# Second_vehicle.net
KiCad netlist of a schematic drawn in EasyEDA
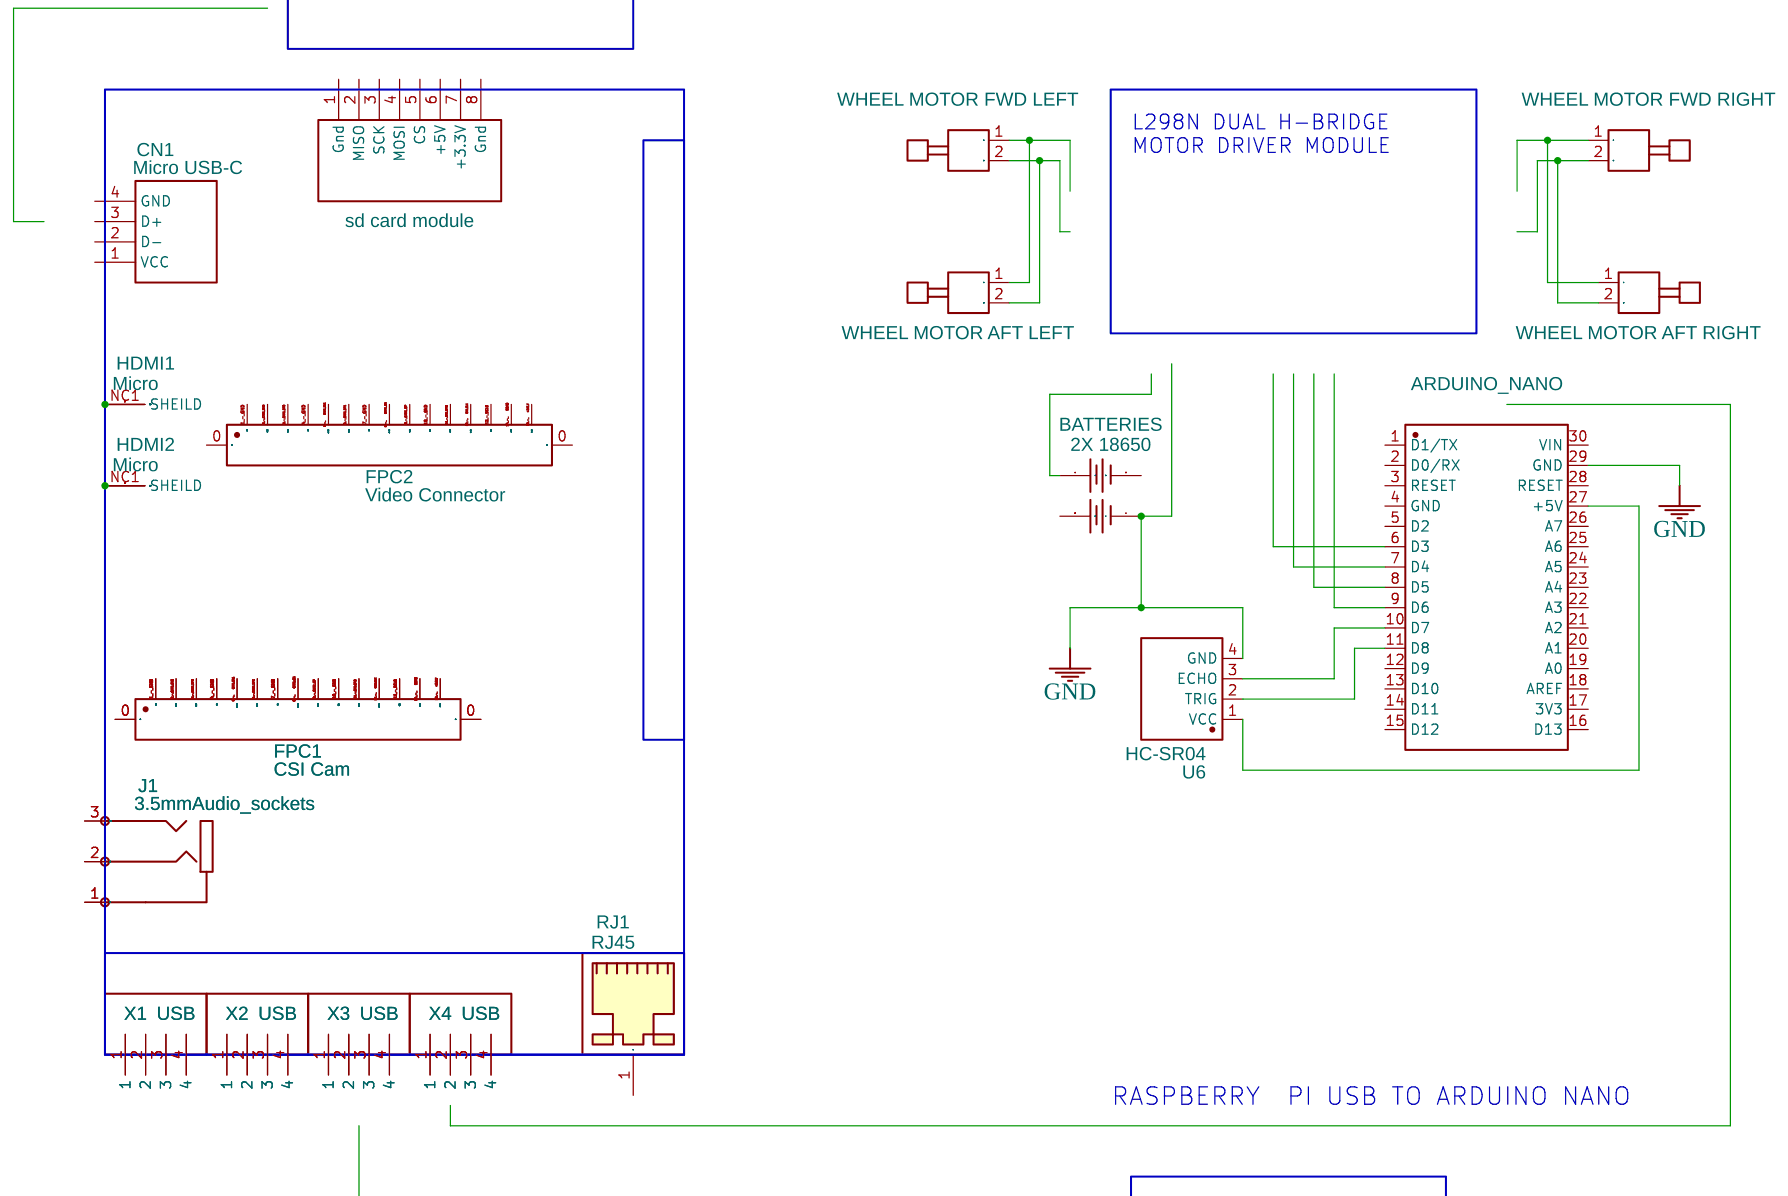
[diagram p0: schematic sheet]

(export (version "E")
  (design (tool "Eeschema 10.0.6"))
  (components
    (comp (ref "BATTERIES")
      (value "2X 18650")
      (fields
        (field (name "Manufacturer Part") "BH-18650-A1BJ034")
        (field (name "Manufacturer") "MYOUNG(美阳)")
      )
      (libsource (lib "") (part "BH-18650-A1BJ034"))
    )
    (comp (ref "CN1")
      (value "Micro USB-C")
      (fields (field (name "Manufacturer Part") "USB-CONN-AF-LCP") (field (name "Manufacturer") "ValuePro"))
      (libsource (lib "") (part "Unknown_90_-1680"))
    )
    (comp (ref "FPC1")
      (value "CSI Cam")
      (fields (field (name "Manufacturer Part") "F1003WR-S-15PNLNG1GB0R") (field (name "Manufacturer") "HR"))
      (libsource (lib "") (part "Unknown_150_-1435"))
    )
    (comp (ref "FPC2")
      (value "Video Connector")
      (fields (field (name "Manufacturer Part") "F1003WR-S-15PNLNG1GB0R") (field (name "Manufacturer") "HR"))
      (libsource (lib "") (part "Unknown_195_-1570"))
    )
    (comp (ref "HDMI1")
      (value "Micro")
      (fields (field (name "Manufacturer Part") "?"))
      (libsource (lib "") (part "Unknown_75_-1590"))
    )
    (comp (ref "HDMI2")
      (value "Micro")
      (fields (field (name "Manufacturer Part") "?"))
      (libsource (lib "") (part "Unknown_75_-1550"))
    )
    (comp (ref "J1")
      (value "3.5mmAudio_sockets")
      (fields
        (field (name "Manufacturer Part") "3.5mmAudio sockets PJ325")
        (field (name "Manufacturer") "BOOMELE")
      )
      (libsource (lib "") (part "Unknown_55_-1365"))
    )
    (comp (ref "RJ1")
      (value "RJ45")
      (fields (field (name "Manufacturer Part") "?"))
      (libsource (lib "") (part "Unknown_325_-1280"))
    )
    (comp (ref "U1") (value "ARDUINO_NANO") (libsource (lib "") (part "ARDUINO_NANO")))
    (comp (ref "U2")
      (value "WHEEL MOTOR FWD LEFT")
      (fields (field (name "Manufacturer Part") "LCM04084521-B1") (field (name "Manufacturer") "LEADER(立得)"))
      (libsource (lib "") (part "LCM04084521-B1_1"))
    )
    (comp (ref "U3")
      (value "WHEEL MOTOR FWD RIGHT")
      (fields (field (name "Manufacturer Part") "LCM04084521-B1") (field (name "Manufacturer") "LEADER(立得)"))
      (libsource (lib "") (part "LCM04084521-B1"))
    )
    (comp (ref "U4")
      (value "WHEEL MOTOR AFT LEFT")
      (fields (field (name "Manufacturer Part") "LCM04084521-B1") (field (name "Manufacturer") "LEADER(立得)"))
      (libsource (lib "") (part "LCM04084521-B1_1"))
    )
    (comp (ref "U5")
      (value "WHEEL MOTOR AFT RIGHT")
      (fields (field (name "Manufacturer Part") "LCM04084521-B1") (field (name "Manufacturer") "LEADER(立得)"))
      (libsource (lib "") (part "LCM04084521-B1"))
    )
    (comp (ref "U6")
      (value "HC-SR04")
      (fields (field (name "Manufacturer") "Universal Microelectronics"))
      (libsource (lib "") (part "HC-SR04"))
    )
    (comp (ref "U7") (value "sd card module") (libsource (lib "") (part "Unknown_205_-1735")))
    (comp (ref "X1")
      (value "USB")
      (fields (field (name "Manufacturer Part") "?"))
      (libsource (lib "") (part "Unknown_80_-1275"))
    )
    (comp (ref "X2")
      (value "USB")
      (fields (field (name "Manufacturer Part") "?"))
      (libsource (lib "") (part "Unknown_130_-1275"))
    )
    (comp (ref "X3")
      (value "USB")
      (fields (field (name "Manufacturer Part") "?"))
      (libsource (lib "") (part "Unknown_180_-1275"))
    )
    (comp (ref "X4")
      (value "USB")
      (fields (field (name "Manufacturer Part") "?"))
      (libsource (lib "") (part "Unknown_230_-1275"))
    )
  )
  (nets
    (net (code "1") (name "GND") (class "Default")
      (node (ref "BATTERIES") (pin "4") (pinfunction "4_4") (pintype "input"))
      (node (ref "U1") (pin "29") (pinfunction "GND_29") (pintype "unspecified"))
      (node (ref "U6") (pin "4") (pinfunction "GND_4") (pintype "unspecified"))
    )
    (net (code "2") (name "Net-(HDMI1-SHEILD-PadNC1)") (class "Default")
      (node (ref "HDMI1") (pin "NC1") (pinfunction "SHEILD_NC1") (pintype "bidirectional"))
      (node (ref "HDMI1") (pin "NC2") (pinfunction "SHEILD_NC2") (pintype "bidirectional"))
      (node (ref "HDMI1") (pin "NC3") (pinfunction "SHEILD_NC3") (pintype "bidirectional"))
      (node (ref "HDMI1") (pin "NC4") (pinfunction "SHEILD_NC4") (pintype "bidirectional"))
    )
    (net (code "3") (name "Net-(HDMI2-SHEILD-PadNC1)") (class "Default")
      (node (ref "HDMI2") (pin "NC1") (pinfunction "SHEILD_NC1") (pintype "bidirectional"))
      (node (ref "HDMI2") (pin "NC2") (pinfunction "SHEILD_NC2") (pintype "bidirectional"))
      (node (ref "HDMI2") (pin "NC3") (pinfunction "SHEILD_NC3") (pintype "bidirectional"))
      (node (ref "HDMI2") (pin "NC4") (pinfunction "SHEILD_NC4") (pintype "bidirectional"))
    )
    (net (code "4") (name "Net-(U1-+5V)") (class "Default")
      (node (ref "U1") (pin "27") (pinfunction "+5V_27") (pintype "unspecified"))
      (node (ref "U6") (pin "1") (pinfunction "VCC_1") (pintype "unspecified"))
    )
    (net (code "5") (name "Net-(U1-D7)") (class "Default")
      (node (ref "U1") (pin "10") (pinfunction "D7_10") (pintype "unspecified"))
      (node (ref "U6") (pin "3") (pinfunction "ECHO_3") (pintype "unspecified"))
    )
    (net (code "6") (name "Net-(U1-D8)") (class "Default")
      (node (ref "U1") (pin "11") (pinfunction "D8_11") (pintype "unspecified"))
      (node (ref "U6") (pin "2") (pinfunction "TRIG_2") (pintype "unspecified"))
    )
    (net (code "7") (name "Net-(U2-Pad1)") (class "Default")
      (node (ref "U2") (pin "1") (pinfunction "1_1") (pintype "unspecified"))
      (node (ref "U4") (pin "1") (pinfunction "1_1") (pintype "unspecified"))
    )
    (net (code "8") (name "Net-(U2-Pad2)") (class "Default")
      (node (ref "U2") (pin "2") (pinfunction "2_2") (pintype "unspecified"))
      (node (ref "U4") (pin "2") (pinfunction "2_2") (pintype "unspecified"))
    )
    (net (code "9") (name "Net-(U3-Pad1)") (class "Default")
      (node (ref "U3") (pin "1") (pinfunction "1_1") (pintype "unspecified"))
      (node (ref "U5") (pin "1") (pinfunction "1_1") (pintype "unspecified"))
    )
    (net (code "10") (name "Net-(U3-Pad2)") (class "Default")
      (node (ref "U3") (pin "2") (pinfunction "2_2") (pintype "unspecified"))
      (node (ref "U5") (pin "2") (pinfunction "2_2") (pintype "unspecified"))
    )
    (net (code "11") (name "unconnected-(BATTERIES-Pad1)") (class "Default")
      (node (ref "BATTERIES") (pin "1") (pinfunction "1_1") (pintype "input"))
    )
    (net (code "12") (name "unconnected-(BATTERIES-Pad2)") (class "Default")
      (node (ref "BATTERIES") (pin "2") (pinfunction "2_2") (pintype "input"))
    )
    (net (code "13") (name "unconnected-(BATTERIES-Pad3)") (class "Default")
      (node (ref "BATTERIES") (pin "3") (pinfunction "3_3") (pintype "input"))
    )
    (net (code "14") (name "unconnected-(CN1-D+-Pad3)") (class "Default")
      (node (ref "CN1") (pin "3") (pinfunction "D+_3") (pintype "input"))
    )
    (net (code "15") (name "unconnected-(CN1-D--Pad2)") (class "Default")
      (node (ref "CN1") (pin "2") (pinfunction "D-_2") (pintype "input"))
    )
    (net (code "16") (name "unconnected-(CN1-GND-Pad4)") (class "Default")
      (node (ref "CN1") (pin "4") (pinfunction "GND_4") (pintype "input"))
    )
    (net (code "17") (name "unconnected-(CN1-VCC-Pad1)") (class "Default")
      (node (ref "CN1") (pin "1") (pinfunction "VCC_1") (pintype "input"))
    )
    (net (code "18") (name "unconnected-(FPC1-Pad0)") (class "Default")
      (node (ref "FPC1") (pin "0") (pinfunction "0_0") (pintype "unspecified"))
    )
    (net (code "19") (name "unconnected-(FPC1-Pad0)_1") (class "Default")
      (node (ref "FPC1") (pin "0") (pinfunction "0_0") (pintype "unspecified"))
    )
    (net (code "20") (name "unconnected-(FPC1-Pad1_-_GND)") (class "Default")
      (node (ref "FPC1") (pin "1_-_GND") (pinfunction "1_-_GND_1_-_GND") (pintype "unspecified"))
    )
    (net (code "21") (name "unconnected-(FPC1-Pad2_-_CAM1_DN0)") (class "Default")
      (node (ref "FPC1") (pin "2_-_CAM1_DN0") (pinfunction "2_-_CAM1_DN0_2_-_CAM1_DN0") (pintype "unspecified"))
    )
    (net (code "22") (name "unconnected-(FPC1-Pad3_-_CAM1_DP0)") (class "Default")
      (node (ref "FPC1") (pin "3_-_CAM1_DP0") (pinfunction "3_-_CAM1_DP0_3_-_CAM1_DP0") (pintype "unspecified"))
    )
    (net (code "23") (name "unconnected-(FPC1-Pad4_-_GND)") (class "Default")
      (node (ref "FPC1") (pin "4_-_GND") (pinfunction "4_-_GND_4_-_GND") (pintype "unspecified"))
    )
    (net (code "24") (name "unconnected-(FPC1-Pad5_-_	CAM1_DN1)") (class "Default")
      (node (ref "FPC1") (pin "5_-_	CAM1_DN1") (pinfunction "5_-_	CAM1_DN1_5_-_	CAM1_DN1") (pintype "unspecified"))
    )
    (net (code "25") (name "unconnected-(FPC1-Pad6_-_CAM1_DP1)") (class "Default")
      (node (ref "FPC1") (pin "6_-_CAM1_DP1") (pinfunction "6_-_CAM1_DP1_6_-_CAM1_DP1") (pintype "unspecified"))
    )
    (net (code "26") (name "unconnected-(FPC1-Pad7_-_GND)") (class "Default")
      (node (ref "FPC1") (pin "7_-_GND") (pinfunction "7_-_GND_7_-_GND") (pintype "unspecified"))
    )
    (net (code "27") (name "unconnected-(FPC1-Pad8_-_	CAM1_CN)") (class "Default")
      (node (ref "FPC1") (pin "8_-_	CAM1_CN") (pinfunction "8_-_	CAM1_CN_8_-_	CAM1_CN") (pintype "unspecified"))
    )
    (net (code "28") (name "unconnected-(FPC1-Pad9_-_CAM1_CP)") (class "Default")
      (node (ref "FPC1") (pin "9_-_CAM1_CP") (pinfunction "9_-_CAM1_CP_9_-_CAM1_CP") (pintype "unspecified"))
    )
    (net (code "29") (name "unconnected-(FPC1-Pad10_-_GND)") (class "Default")
      (node (ref "FPC1") (pin "10_-_GND") (pinfunction "10_-_GND_10_-_GND") (pintype "unspecified"))
    )
    (net (code "30") (name "unconnected-(FPC1-Pad11_-_CAM_GPIO)") (class "Default")
      (node (ref "FPC1") (pin "11_-_CAM_GPIO") (pinfunction "11_-_CAM_GPIO_11_-_CAM_GPIO") (pintype "unspecified"))
    )
    (net (code "31") (name "unconnected-(FPC1-Pad12_-_	CAM_CLK)") (class "Default")
      (node (ref "FPC1") (pin "12_-_	CAM_CLK") (pinfunction "12_-_	CAM_CLK_12_-_	CAM_CLK") (pintype "unspecified"))
    )
    (net (code "32") (name "unconnected-(FPC1-Pad13_-_SCL0)") (class "Default")
      (node (ref "FPC1") (pin "13_-_SCL0") (pinfunction "13_-_SCL0_13_-_SCL0") (pintype "unspecified"))
    )
    (net (code "33") (name "unconnected-(FPC1-Pad14_-_	SDA0)") (class "Default")
      (node (ref "FPC1") (pin "14_-_	SDA0") (pinfunction "14_-_	SDA0_14_-_	SDA0") (pintype "unspecified"))
    )
    (net (code "34") (name "unconnected-(FPC1-Pad15_-_	+3.3_V)") (class "Default")
      (node (ref "FPC1") (pin "15_-_	+3.3_V") (pinfunction "15_-_	+3.3_V_15_-_	+3.3_V") (pintype "unspecified"))
    )
    (net (code "35") (name "unconnected-(FPC2-Pad0)") (class "Default")
      (node (ref "FPC2") (pin "0") (pinfunction "0_0") (pintype "unspecified"))
    )
    (net (code "36") (name "unconnected-(FPC2-Pad0)_1") (class "Default")
      (node (ref "FPC2") (pin "0") (pinfunction "0_0") (pintype "unspecified"))
    )
    (net (code "37") (name "unconnected-(FPC2-Pad1_-_GND)") (class "Default")
      (node (ref "FPC2") (pin "1_-_GND") (pinfunction "1_-_GND_1_-_GND") (pintype "unspecified"))
    )
    (net (code "38") (name "unconnected-(FPC2-Pad2_-_CAM1_DN0)") (class "Default")
      (node (ref "FPC2") (pin "2_-_CAM1_DN0") (pinfunction "2_-_CAM1_DN0_2_-_CAM1_DN0") (pintype "unspecified"))
    )
    (net (code "39") (name "unconnected-(FPC2-Pad3_-_CAM1_DP0)") (class "Default")
      (node (ref "FPC2") (pin "3_-_CAM1_DP0") (pinfunction "3_-_CAM1_DP0_3_-_CAM1_DP0") (pintype "unspecified"))
    )
    (net (code "40") (name "unconnected-(FPC2-Pad4_-_GND)") (class "Default")
      (node (ref "FPC2") (pin "4_-_GND") (pinfunction "4_-_GND_4_-_GND") (pintype "unspecified"))
    )
    (net (code "41") (name "unconnected-(FPC2-Pad5_-_	CAM1_DN1)") (class "Default")
      (node (ref "FPC2") (pin "5_-_	CAM1_DN1") (pinfunction "5_-_	CAM1_DN1_5_-_	CAM1_DN1") (pintype "unspecified"))
    )
    (net (code "42") (name "unconnected-(FPC2-Pad6_-_CAM1_DP1)") (class "Default")
      (node (ref "FPC2") (pin "6_-_CAM1_DP1") (pinfunction "6_-_CAM1_DP1_6_-_CAM1_DP1") (pintype "unspecified"))
    )
    (net (code "43") (name "unconnected-(FPC2-Pad7_-_GND)") (class "Default")
      (node (ref "FPC2") (pin "7_-_GND") (pinfunction "7_-_GND_7_-_GND") (pintype "unspecified"))
    )
    (net (code "44") (name "unconnected-(FPC2-Pad8_-_	CAM1_CN)") (class "Default")
      (node (ref "FPC2") (pin "8_-_	CAM1_CN") (pinfunction "8_-_	CAM1_CN_8_-_	CAM1_CN") (pintype "unspecified"))
    )
    (net (code "45") (name "unconnected-(FPC2-Pad9_-_CAM1_CP)") (class "Default")
      (node (ref "FPC2") (pin "9_-_CAM1_CP") (pinfunction "9_-_CAM1_CP_9_-_CAM1_CP") (pintype "unspecified"))
    )
    (net (code "46") (name "unconnected-(FPC2-Pad10_-_GND)") (class "Default")
      (node (ref "FPC2") (pin "10_-_GND") (pinfunction "10_-_GND_10_-_GND") (pintype "unspecified"))
    )
    (net (code "47") (name "unconnected-(FPC2-Pad11_-_CAM_GPIO)") (class "Default")
      (node (ref "FPC2") (pin "11_-_CAM_GPIO") (pinfunction "11_-_CAM_GPIO_11_-_CAM_GPIO") (pintype "unspecified"))
    )
    (net (code "48") (name "unconnected-(FPC2-Pad12_-_	CAM_CLK)") (class "Default")
      (node (ref "FPC2") (pin "12_-_	CAM_CLK") (pinfunction "12_-_	CAM_CLK_12_-_	CAM_CLK") (pintype "unspecified"))
    )
    (net (code "49") (name "unconnected-(FPC2-Pad13_-_SCL0)") (class "Default")
      (node (ref "FPC2") (pin "13_-_SCL0") (pinfunction "13_-_SCL0_13_-_SCL0") (pintype "unspecified"))
    )
    (net (code "50") (name "unconnected-(FPC2-Pad14_-_	SDA0)") (class "Default")
      (node (ref "FPC2") (pin "14_-_	SDA0") (pinfunction "14_-_	SDA0_14_-_	SDA0") (pintype "unspecified"))
    )
    (net (code "51") (name "unconnected-(FPC2-Pad15_-_	+3.3_V)") (class "Default")
      (node (ref "FPC2") (pin "15_-_	+3.3_V") (pinfunction "15_-_	+3.3_V_15_-_	+3.3_V") (pintype "unspecified"))
    )
    (net (code "52") (name "unconnected-(J1-12V-Pad2)") (class "Default")
      (node (ref "J1") (pin "2") (pinfunction "12V_2") (pintype "input"))
    )
    (net (code "53") (name "unconnected-(J1-GND-Pad1)") (class "Default")
      (node (ref "J1") (pin "1") (pinfunction "GND_1") (pintype "input"))
    )
    (net (code "54") (name "unconnected-(J1-SIGNAL-Pad3)") (class "Default")
      (node (ref "J1") (pin "3") (pinfunction "SIGNAL_3") (pintype "input"))
    )
    (net (code "55") (name "unconnected-(RJ1-Pad1)") (class "Default")
      (node (ref "RJ1") (pin "1") (pinfunction "1_1") (pintype "unspecified"))
    )
    (net (code "56") (name "unconnected-(U1-3V3-Pad17)") (class "Default")
      (node (ref "U1") (pin "17") (pinfunction "3V3_17") (pintype "unspecified"))
    )
    (net (code "57") (name "unconnected-(U1-A0-Pad19)") (class "Default")
      (node (ref "U1") (pin "19") (pinfunction "A0_19") (pintype "unspecified"))
    )
    (net (code "58") (name "unconnected-(U1-A1-Pad20)") (class "Default")
      (node (ref "U1") (pin "20") (pinfunction "A1_20") (pintype "unspecified"))
    )
    (net (code "59") (name "unconnected-(U1-A2-Pad21)") (class "Default")
      (node (ref "U1") (pin "21") (pinfunction "A2_21") (pintype "unspecified"))
    )
    (net (code "60") (name "unconnected-(U1-A3-Pad22)") (class "Default")
      (node (ref "U1") (pin "22") (pinfunction "A3_22") (pintype "unspecified"))
    )
    (net (code "61") (name "unconnected-(U1-A4-Pad23)") (class "Default")
      (node (ref "U1") (pin "23") (pinfunction "A4_23") (pintype "unspecified"))
    )
    (net (code "62") (name "unconnected-(U1-A5-Pad24)") (class "Default")
      (node (ref "U1") (pin "24") (pinfunction "A5_24") (pintype "unspecified"))
    )
    (net (code "63") (name "unconnected-(U1-A6-Pad25)") (class "Default")
      (node (ref "U1") (pin "25") (pinfunction "A6_25") (pintype "unspecified"))
    )
    (net (code "64") (name "unconnected-(U1-A7-Pad26)") (class "Default")
      (node (ref "U1") (pin "26") (pinfunction "A7_26") (pintype "unspecified"))
    )
    (net (code "65") (name "unconnected-(U1-AREF-Pad18)") (class "Default")
      (node (ref "U1") (pin "18") (pinfunction "AREF_18") (pintype "unspecified"))
    )
    (net (code "66") (name "unconnected-(U1-D0{slash}RX-Pad2)") (class "Default")
      (node (ref "U1") (pin "2") (pinfunction "D0/RX_2") (pintype "unspecified"))
    )
    (net (code "67") (name "unconnected-(U1-D1{slash}TX-Pad1)") (class "Default")
      (node (ref "U1") (pin "1") (pinfunction "D1/TX_1") (pintype "unspecified"))
    )
    (net (code "68") (name "unconnected-(U1-D2-Pad5)") (class "Default")
      (node (ref "U1") (pin "5") (pinfunction "D2_5") (pintype "unspecified"))
    )
    (net (code "69") (name "unconnected-(U1-D3-Pad6)") (class "Default")
      (node (ref "U1") (pin "6") (pinfunction "D3_6") (pintype "unspecified"))
    )
    (net (code "70") (name "unconnected-(U1-D4-Pad7)") (class "Default")
      (node (ref "U1") (pin "7") (pinfunction "D4_7") (pintype "unspecified"))
    )
    (net (code "71") (name "unconnected-(U1-D5-Pad8)") (class "Default")
      (node (ref "U1") (pin "8") (pinfunction "D5_8") (pintype "unspecified"))
    )
    (net (code "72") (name "unconnected-(U1-D6-Pad9)") (class "Default")
      (node (ref "U1") (pin "9") (pinfunction "D6_9") (pintype "unspecified"))
    )
    (net (code "73") (name "unconnected-(U1-D9-Pad12)") (class "Default")
      (node (ref "U1") (pin "12") (pinfunction "D9_12") (pintype "unspecified"))
    )
    (net (code "74") (name "unconnected-(U1-D10-Pad13)") (class "Default")
      (node (ref "U1") (pin "13") (pinfunction "D10_13") (pintype "unspecified"))
    )
    (net (code "75") (name "unconnected-(U1-D11-Pad14)") (class "Default")
      (node (ref "U1") (pin "14") (pinfunction "D11_14") (pintype "unspecified"))
    )
    (net (code "76") (name "unconnected-(U1-D12-Pad15)") (class "Default")
      (node (ref "U1") (pin "15") (pinfunction "D12_15") (pintype "unspecified"))
    )
    (net (code "77") (name "unconnected-(U1-D13-Pad16)") (class "Default")
      (node (ref "U1") (pin "16") (pinfunction "D13_16") (pintype "unspecified"))
    )
    (net (code "78") (name "unconnected-(U1-GND-Pad4)") (class "Default")
      (node (ref "U1") (pin "4") (pinfunction "GND_4") (pintype "unspecified"))
    )
    (net (code "79") (name "unconnected-(U1-RESET-Pad3)") (class "Default")
      (node (ref "U1") (pin "3") (pinfunction "RESET_3") (pintype "unspecified"))
    )
    (net (code "80") (name "unconnected-(U1-RESET-Pad28)") (class "Default")
      (node (ref "U1") (pin "28") (pinfunction "RESET_28") (pintype "unspecified"))
    )
    (net (code "81") (name "unconnected-(U1-VIN-Pad30)") (class "Default")
      (node (ref "U1") (pin "30") (pinfunction "VIN_30") (pintype "unspecified"))
    )
    (net (code "82") (name "unconnected-(U7-+3.3V-Pad7)") (class "Default")
      (node (ref "U7") (pin "7") (pinfunction "+3.3V_7") (pintype "unspecified"))
    )
    (net (code "83") (name "unconnected-(U7-+5V-Pad6)") (class "Default")
      (node (ref "U7") (pin "6") (pinfunction "+5V_6") (pintype "unspecified"))
    )
    (net (code "84") (name "unconnected-(U7-CS-Pad5)") (class "Default")
      (node (ref "U7") (pin "5") (pinfunction "CS_5") (pintype "unspecified"))
    )
    (net (code "85") (name "unconnected-(U7-Gnd-Pad1)") (class "Default")
      (node (ref "U7") (pin "1") (pinfunction "Gnd_1") (pintype "unspecified"))
    )
    (net (code "86") (name "unconnected-(U7-Gnd-Pad8)") (class "Default")
      (node (ref "U7") (pin "8") (pinfunction "Gnd_8") (pintype "unspecified"))
    )
    (net (code "87") (name "unconnected-(U7-MISO-Pad2)") (class "Default")
      (node (ref "U7") (pin "2") (pinfunction "MISO_2") (pintype "unspecified"))
    )
    (net (code "88") (name "unconnected-(U7-MOSI-Pad4)") (class "Default")
      (node (ref "U7") (pin "4") (pinfunction "MOSI_4") (pintype "unspecified"))
    )
    (net (code "89") (name "unconnected-(U7-SCK-Pad3)") (class "Default")
      (node (ref "U7") (pin "3") (pinfunction "SCK_3") (pintype "unspecified"))
    )
    (net (code "90") (name "unconnected-(X1-Pad1)") (class "Default")
      (node (ref "X1") (pin "1") (pinfunction "1_1") (pintype "unspecified"))
    )
    (net (code "91") (name "unconnected-(X1-Pad2)") (class "Default")
      (node (ref "X1") (pin "2") (pinfunction "2_2") (pintype "unspecified"))
    )
    (net (code "92") (name "unconnected-(X1-Pad3)") (class "Default")
      (node (ref "X1") (pin "3") (pinfunction "3_3") (pintype "unspecified"))
    )
    (net (code "93") (name "unconnected-(X1-Pad4)") (class "Default")
      (node (ref "X1") (pin "4") (pinfunction "4_4") (pintype "unspecified"))
    )
    (net (code "94") (name "unconnected-(X2-Pad1)") (class "Default")
      (node (ref "X2") (pin "1") (pinfunction "1_1") (pintype "unspecified"))
    )
    (net (code "95") (name "unconnected-(X2-Pad2)") (class "Default")
      (node (ref "X2") (pin "2") (pinfunction "2_2") (pintype "unspecified"))
    )
    (net (code "96") (name "unconnected-(X2-Pad3)") (class "Default")
      (node (ref "X2") (pin "3") (pinfunction "3_3") (pintype "unspecified"))
    )
    (net (code "97") (name "unconnected-(X2-Pad4)") (class "Default")
      (node (ref "X2") (pin "4") (pinfunction "4_4") (pintype "unspecified"))
    )
    (net (code "98") (name "unconnected-(X3-Pad1)") (class "Default")
      (node (ref "X3") (pin "1") (pinfunction "1_1") (pintype "unspecified"))
    )
    (net (code "99") (name "unconnected-(X3-Pad2)") (class "Default")
      (node (ref "X3") (pin "2") (pinfunction "2_2") (pintype "unspecified"))
    )
    (net (code "100") (name "unconnected-(X3-Pad3)") (class "Default")
      (node (ref "X3") (pin "3") (pinfunction "3_3") (pintype "unspecified"))
    )
    (net (code "101") (name "unconnected-(X3-Pad4)") (class "Default")
      (node (ref "X3") (pin "4") (pinfunction "4_4") (pintype "unspecified"))
    )
    (net (code "102") (name "unconnected-(X4-Pad1)") (class "Default")
      (node (ref "X4") (pin "1") (pinfunction "1_1") (pintype "unspecified"))
    )
    (net (code "103") (name "unconnected-(X4-Pad2)") (class "Default")
      (node (ref "X4") (pin "2") (pinfunction "2_2") (pintype "unspecified"))
    )
    (net (code "104") (name "unconnected-(X4-Pad3)") (class "Default")
      (node (ref "X4") (pin "3") (pinfunction "3_3") (pintype "unspecified"))
    )
    (net (code "105") (name "unconnected-(X4-Pad4)") (class "Default")
      (node (ref "X4") (pin "4") (pinfunction "4_4") (pintype "unspecified"))
    )
  )
)
